# buzzer.net
KiCad netlist of a schematic drawn in Altium Designer
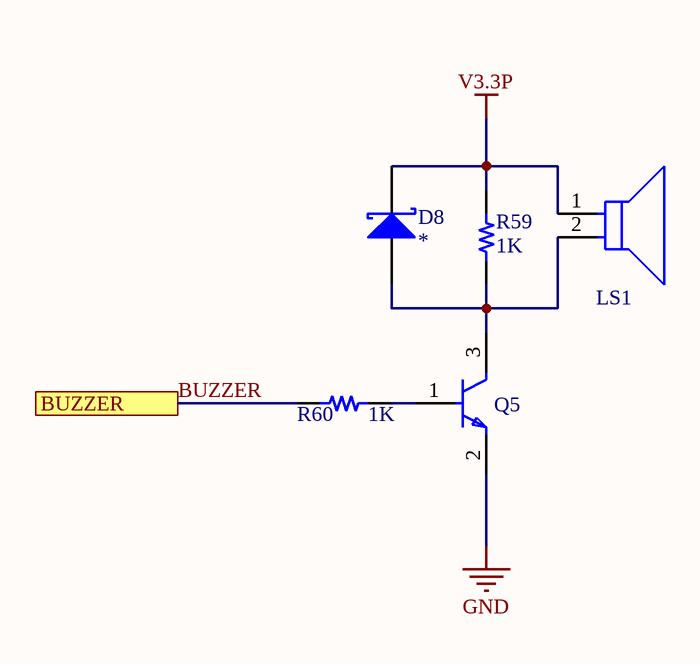
[diagram p0: buzzer.SchDoc]

(export (version "E")
  (design (tool "Eeschema 10.0.6"))
  (components
    (comp (ref "D8")
      (value "*")
      (footprint "Rohm_TUMD2M_MFG")
      (fields (field (name "MF") "Toshiba") (field (name "MP") "CUHS20F30,H3F"))
      (libsource (lib "Diode") (part "Schottky Diode"))
    )
    (comp (ref "LS1")
      (value "Buzzer")
      (footprint "Murata_0_MFG")
      (description "SPEAK AUDIO PIEZO TRANSDUCER 30V TH")
      (fields (field (name "MP") "PS1240P02BT") (field (name "MF") "TDK"))
      (libsource (lib "Buzzer") (part "Piezo Buzzers"))
    )
    (comp (ref "Q5")
      (value "N Transistor")
      (footprint "ON_Semiconductor_MA03D_MFG")
      (description "Small Signal Transistor, Bipolar (BJT), Single, NPN")
      (fields (field (name "MF") "Nexperia") (field (name "MP") "MMBT3904,215"))
      (libsource (lib "Transistor") (part "NPN"))
    )
    (comp (ref "R59")
      (value "1K")
      (footprint "RES 0603_1608")
      (description "SMT Resistor")
      (fields (field (name "MF") "YAGEO") (field (name "MP") "AC0603FR-071KL"))
      (libsource (lib "Resistor") (part "Resistor"))
    )
    (comp (ref "R60")
      (value "1K")
      (footprint "RES 0603_1608")
      (description "SMT Resistor")
      (fields (field (name "MF") "YAGEO") (field (name "MP") "AC0603FR-071KL"))
      (libsource (lib "Resistor") (part "Resistor"))
    )
  )
  (nets
    (net (code "1") (name "/BUZZER") (class "Default")
      (node (ref "R60") (pin "1") (pinfunction "1_1") (pintype "passive"))
    )
    (net (code "2") (name "GND") (class "Default")
      (node (ref "Q5") (pin "2") (pinfunction "E_2") (pintype "passive"))
    )
    (net (code "3") (name "Net-(D8-A)") (class "Default")
      (node (ref "D8") (pin "2") (pinfunction "A_2") (pintype "passive"))
      (node (ref "LS1") (pin "2") (pinfunction "2_2") (pintype "passive"))
      (node (ref "Q5") (pin "3") (pinfunction "C_3") (pintype "passive"))
      (node (ref "R59") (pin "1") (pinfunction "1_1") (pintype "passive"))
    )
    (net (code "4") (name "Net-(Q5-B)") (class "Default")
      (node (ref "Q5") (pin "1") (pinfunction "B_1") (pintype "passive"))
      (node (ref "R60") (pin "2") (pinfunction "2_2") (pintype "passive"))
    )
    (net (code "5") (name "V3.3P") (class "Default")
      (node (ref "D8") (pin "1") (pinfunction "K_1") (pintype "passive"))
      (node (ref "LS1") (pin "1") (pinfunction "1_1") (pintype "passive"))
      (node (ref "R59") (pin "2") (pinfunction "2_2") (pintype "passive"))
    )
  )
)
